# Sheet1.net
KiCad netlist of a schematic drawn in Altium Designer
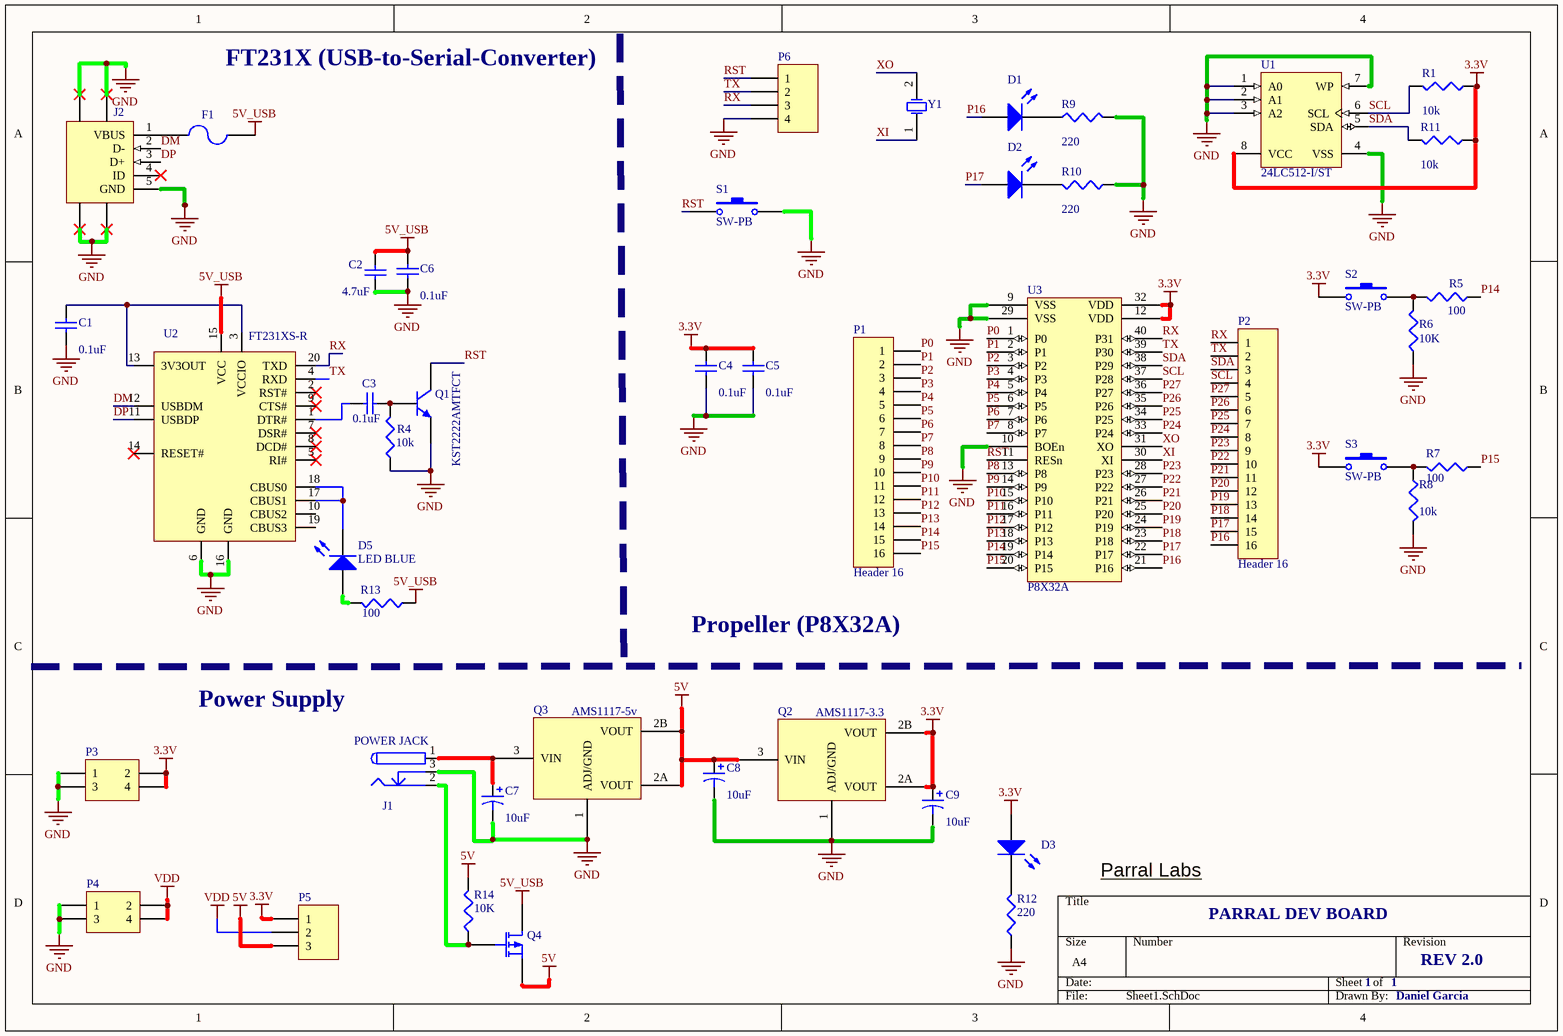
[diagram p0: Sheet1.SchDoc]

(export (version "E")
  (design (tool "Eeschema 10.0.6"))
  (components
    (comp (ref "C1")
      (value "0.1uF")
      (footprint "0603 - Old1")
      (description "0.1uF Capacitor 0603")
      (fields (field (name "PARTNUMBER") "478-1395-1-ND") (field (name "PUBLISHER") "Altium Limited"))
      (libsource (lib "Miscellaneous Devices") (part "Cap Semi"))
    )
    (comp (ref "C2")
      (value "4.7uF")
      (footprint "0603 - Old1")
      (description "4.7µF 25V Ceramic Capacitor X5R 0603")
      (fields
        (field (name "MANUFACTURERPARTNUMBER") "CL21A475KAQNNNE")
        (field (name "PUBLISHER") "Altium Limited")
      )
      (libsource (lib "Miscellaneous Devices") (part "Cap Semi"))
    )
    (comp (ref "C3")
      (value "0.1uF")
      (footprint "0603 - Old1")
      (description "0.1uF Capacitor 0603")
      (fields (field (name "PARTNUMBER") "478-1395-1-ND") (field (name "PUBLISHER") "Altium Limited"))
      (libsource (lib "Miscellaneous Devices") (part "Cap Semi"))
    )
    (comp (ref "C4")
      (value "0.1uF")
      (footprint "0603 - Old1")
      (description "0.1uF Capacitor 0603")
      (fields (field (name "PARTNUMBER") "478-1395-1-ND") (field (name "PUBLISHER") "Altium Limited"))
      (libsource (lib "Miscellaneous Devices") (part "Cap Semi"))
    )
    (comp (ref "C5")
      (value "0.1uF")
      (footprint "0603 - Old1")
      (description "0.1uF Capacitor 0603")
      (fields (field (name "PARTNUMBER") "478-1395-1-ND") (field (name "PUBLISHER") "Altium Limited"))
      (libsource (lib "Miscellaneous Devices") (part "Cap Semi"))
    )
    (comp (ref "C6")
      (value "0.1uF")
      (footprint "0603 - Old1")
      (description "0.1uF Capacitor 0603")
      (fields (field (name "PARTNUMBER") "478-1395-1-ND") (field (name "PUBLISHER") "Altium Limited"))
      (libsource (lib "Miscellaneous Devices") (part "Cap Semi"))
    )
    (comp (ref "C7")
      (value "10uF")
      (footprint "C0805")
      (description "10µF Molded Tantalum Capacitors 10V 0805")
      (fields (field (name "PARTNUMBER") "399-3684-1-ND") (field (name "PUBLISHER") "Altium Limited"))
      (libsource (lib "Miscellaneous Devices") (part "Cap Pol3"))
    )
    (comp (ref "C8")
      (value "10uF")
      (footprint "C0805")
      (description "10µF Molded Tantalum Capacitors 10V 0805")
      (fields (field (name "PARTNUMBER") "399-3684-1-ND") (field (name "PUBLISHER") "Altium Limited"))
      (libsource (lib "Miscellaneous Devices") (part "Cap Pol3"))
    )
    (comp (ref "C9")
      (value "10uF")
      (footprint "C0805")
      (description "10µF Molded Tantalum Capacitors 10V 0805")
      (fields (field (name "PARTNUMBER") "399-3684-1-ND") (field (name "PUBLISHER") "Altium Limited"))
      (libsource (lib "Miscellaneous Devices") (part "Cap Pol3"))
    )
    (comp (ref "D1")
      (value "LED GREEN")
      (footprint "LED-0603")
      (description "LED 0603")
      (fields (field (name "PUBLISHER") "Altium Limited"))
      (libsource (lib "Miscellaneous Devices") (part "LED2"))
    )
    (comp (ref "D2")
      (value "LED BLUE")
      (footprint "LED-0603")
      (description "LED 0603")
      (fields (field (name "PUBLISHER") "Altium Limited"))
      (libsource (lib "Miscellaneous Devices") (part "LED0"))
    )
    (comp (ref "D3")
      (value "LED RED")
      (footprint "LED-0603")
      (description "LED 0603")
      (fields (field (name "PUBLISHER") "Altium Limited"))
      (libsource (lib "Miscellaneous Devices") (part "LED2"))
    )
    (comp (ref "D5")
      (value "LED BLUE")
      (footprint "LED-0603")
      (description "LED 0603")
      (fields (field (name "PUBLISHER") "Altium Limited"))
      (libsource (lib "Miscellaneous Devices") (part "LED0"))
    )
    (comp (ref "F1")
      (value "PTC")
      (footprint "MF-MSMF050-2")
      (description "PTC RESETTABLE .50A 15V 1812")
      (fields
        (field (name "MANUFACTURER PART NUMBER") "MF-MSMF050-2")
        (field (name "MANUFACTURER") "Bourns Inc.")
        (field (name "PUBLISHER") "Altium Limited")
      )
      (libsource (lib "Miscellaneous Devices") (part "Fuse 2"))
    )
    (comp (ref "J1")
      (value "POWER JACK")
      (footprint "PWR JACK")
      (description "POWER JACK 5.5x2.1mm")
      (libsource (lib "dc-powerjack") (part "Component_1"))
    )
    (comp (ref "J2")
      (value "USB - micro B")
      (footprint "micro B USB 2.0")
      (description "CONN USB MICRO B RECPT SMT R/A")
      (fields
        (field (name "MANUFACTURER PART NUMBER") "10118192-0001LF")
        (field (name "PARTNUMBER") "609-4613-1-ND")
      )
      (libsource (lib "MICRO-USB") (part "USB MICRO B RECPT SMT"))
    )
    (comp (ref "P1")
      (value "Header 16")
      (footprint "HDR1X16")
      (description "Header, 16-Pin")
      (fields (field (name "PUBLISHER") "Altium Limited"))
      (libsource (lib "Miscellaneous Connectors") (part "Header 16"))
    )
    (comp (ref "P2")
      (value "Header 16")
      (footprint "HDR1X16")
      (description "Header, 16-Pin")
      (fields (field (name "PUBLISHER") "Altium Limited"))
      (libsource (lib "") (part "Header 16_1"))
    )
    (comp (ref "P3")
      (value "Header 2X2")
      (footprint "HDR2X2")
      (description "Header, 2-Pin, Dual row")
      (fields (field (name "PUBLISHER") "Altium Limited"))
      (libsource (lib "Miscellaneous Connectors") (part "Header 2X2"))
    )
    (comp (ref "P4")
      (value "Header 2X2")
      (footprint "HDR2X2")
      (description "Header, 2-Pin, Dual row")
      (fields (field (name "PUBLISHER") "Altium Limited"))
      (libsource (lib "Miscellaneous Connectors") (part "Header 2X2"))
    )
    (comp (ref "P5")
      (value "Header 3")
      (footprint "HDR1X3")
      (description "Header, 3-Pin")
      (fields (field (name "PUBLISHER") "Altium Limited"))
      (libsource (lib "Miscellaneous Connectors") (part "Header 3"))
    )
    (comp (ref "P6")
      (value "Header 4")
      (footprint "HDR1X4")
      (description "Header, 4-Pin")
      (fields (field (name "PUBLISHER") "Altium Limited"))
      (libsource (lib "Miscellaneous Connectors") (part "Header 4"))
    )
    (comp (ref "Q1")
      (value "KST2222AMTFCT")
      (footprint "SOT-23B_N")
      (description "TRANS NPN 40V 0.6A SOT-23")
      (fields
        (field (name "MANUFACTURER PART NUMBER") "KST2222AMTF")
        (field (name "MANUFACTURER") "Fairchild/ON Semiconductor")
        (field (name "PUBLISHER") "Altium Limited")
      )
      (libsource (lib "Miscellaneous Devices") (part "QNPN"))
    )
    (comp (ref "Q2")
      (value "AMS1117-3.3")
      (footprint "SOT223_M")
      (description "Linear Voltage Regulator IC Positive Fixed 1 Output 3.3V")
      (fields (field (name "MANUFACTURER") "Advanced Monolithic Systems"))
      (libsource (lib "AS1117") (part "AP1117E33GDICT-ND"))
    )
    (comp (ref "Q3")
      (value "AMS1117-5v")
      (footprint "SOT223_M")
      (description "Linear Voltage Regulator IC Positive Fixed 1 Output 3.3V")
      (fields
        (field (name "MANUFACTURER PART NUMBER") "AMS1117-5.0")
        (field (name "MANUFACTURER") "Advanced Monolithic Systems")
      )
      (libsource (lib "AS1117") (part "AP1117E33GDICT-ND"))
    )
    (comp (ref "Q4")
      (value "ZXMP6A13FTA")
      (footprint "SOT-23-3")
      (description "MOSFET P-CH 60V 0.9A SOT23-3")
      (fields (field (name "PUBLISHER") "Altium Limited"))
      (libsource (lib "Miscellaneous Devices") (part "MOSFET-P"))
    )
    (comp (ref "R1")
      (value "10k")
      (footprint "0603-Resistor")
      (description "RES SMD 10K OHM 5% 1/4W 0603")
      (fields (field (name "Comment") "10K") (field (name "PUBLISHER") "Altium Limited"))
      (libsource (lib "Miscellaneous Devices") (part "Res3"))
    )
    (comp (ref "R4")
      (value "10k")
      (footprint "0603-Resistor")
      (description "RES SMD 10K OHM 5% 1/4W 0603")
      (fields (field (name "Comment") "10K") (field (name "PUBLISHER") "Altium Limited"))
      (libsource (lib "Miscellaneous Devices") (part "Res3"))
    )
    (comp (ref "R5")
      (value "100")
      (footprint "0603-Resistor")
      (description "RES SMD 100 OHM 5% 1/4W 0603")
      (fields (field (name "PARTNUMBER") "RMCF1206JT100RCT-ND") (field (name "PUBLISHER") "Altium Limited"))
      (libsource (lib "Miscellaneous Devices") (part "Res3"))
    )
    (comp (ref "R6")
      (value "10K")
      (footprint "0603-Resistor")
      (description "RES SMD 10K OHM 5% 1/4W 0603")
      (fields (field (name "PARTNUMBER") "311-10KERCT-ND") (field (name "PUBLISHER") "Altium Limited"))
      (libsource (lib "Miscellaneous Devices") (part "Res3"))
    )
    (comp (ref "R7")
      (value "100")
      (footprint "0603-Resistor")
      (description "RES SMD 100 OHM 5% 1/4W 0603")
      (fields (field (name "PUBLISHER") "Altium Limited"))
      (libsource (lib "Miscellaneous Devices") (part "Res3"))
    )
    (comp (ref "R8")
      (value "10k")
      (footprint "R-0603:0603-Resistor")
      (description "RES SMD 10K OHM 5% 1/4W 0603")
      (fields (field (name "Comment") "10K") (field (name "PUBLISHER") "Altium Limited"))
      (libsource (lib "Miscellaneous Devices") (part "Res3"))
    )
    (comp (ref "R9")
      (value "220")
      (footprint "0603-Resistor")
      (description "RES SMD 220 OHM 5% 1/4W 0603")
      (fields (field (name "PUBLISHER") "Altium Limited"))
      (libsource (lib "Miscellaneous Devices") (part "Res3"))
    )
    (comp (ref "R10")
      (value "220")
      (footprint "0603-Resistor")
      (description "RES SMD 220 OHM 5% 1/4W 0603")
      (fields (field (name "PUBLISHER") "Altium Limited"))
      (libsource (lib "Miscellaneous Devices") (part "Res3"))
    )
    (comp (ref "R11")
      (value "10k")
      (footprint "0603-Resistor")
      (description "RES SMD 10K OHM 5% 1/4W 0603")
      (fields (field (name "Comment") "10K") (field (name "PUBLISHER") "Altium Limited"))
      (libsource (lib "Miscellaneous Devices") (part "Res3"))
    )
    (comp (ref "R12")
      (value "220")
      (footprint "0603-Resistor")
      (description "RES SMD 220 OHM 5% 1/4W 0603")
      (fields (field (name "PARTNUMBER") "er  P220ECT-ND") (field (name "PUBLISHER") "Altium Limited"))
      (libsource (lib "Miscellaneous Devices") (part "Res3"))
    )
    (comp (ref "R13")
      (value "100")
      (footprint "0603-Resistor")
      (description "RES SMD 100 OHM 5% 1/4W 0603")
      (fields (field (name "PUBLISHER") "Altium Limited"))
      (libsource (lib "Miscellaneous Devices") (part "Res3"))
    )
    (comp (ref "R14")
      (value "10K")
      (footprint "0603-Resistor")
      (description "RES SMD 10K OHM 5% 1/4W 0603")
      (fields (field (name "PUBLISHER") "Altium Limited"))
      (libsource (lib "Miscellaneous Devices") (part "Res3"))
    )
    (comp (ref "S1")
      (value "SW-PB")
      (footprint "PTS810")
      (description "SWITCH TACTILE SPST-NO 0.05A 12V")
      (fields
        (field (name "MANUFACTURER PART NUMBER") "B3U-1000P")
        (field (name "MANUFACTURER") "Omron Electronics Inc-EMC Div")
        (field (name "PUBLISHER") "Altium Limited")
      )
      (libsource (lib "Miscellaneous Devices") (part "SW-PB"))
    )
    (comp (ref "S2")
      (value "SW-PB")
      (footprint "PTS810")
      (description "SWITCH TACTILE SPST-NO 0.05A 12V")
      (fields
        (field (name "MANUFACTURER PART NUMBER") "B3U-1000P")
        (field (name "MANUFACTURER") "Omron Electronics Inc-EMC Div")
        (field (name "PUBLISHER") "Altium Limited")
      )
      (libsource (lib "Miscellaneous Devices") (part "SW-PB"))
    )
    (comp (ref "S3")
      (value "SW-PB")
      (footprint "PTS810")
      (description "SWITCH TACTILE SPST-NO 0.05A 12V")
      (fields
        (field (name "MANUFACTURER PART NUMBER") "B3U-1000P")
        (field (name "MANUFACTURER") "Omron Electronics Inc-EMC Div")
        (field (name "PUBLISHER") "Altium Limited")
      )
      (libsource (lib "Miscellaneous Devices") (part "SW-PB"))
    )
    (comp (ref "U1")
      (value "24LC512-I/ST")
      (footprint "SOIC-8")
      (description "IC EEPROM 512KBIT 400KHZ 8SOIJ")
      (fields
        (field (name "MANUFACTURER PART NUMBER") "24LC512-I/ST-ND")
        (field (name "PUBLISHER") "Altium Limited")
      )
      (libsource (lib "Microchip Memory I2C Serial EEPROM") (part "24LC256-I/ST"))
    )
    (comp (ref "U2")
      (value "FT231XS-R")
      (description "IC USB SERIAL FULL UART 20SSOP")
      (fields
        (field (name "MANUFACTURER") "FTDI, Future Technology Devices International Ltd")
        (field (name "DIGI-KEY PART NUMBER") "768-1129-1-ND")
      )
      (libsource (lib "FT231XS") (part "FT231XS-R"))
    )
    (comp (ref "U3")
      (value "P8X32A")
      (footprint "DIP-40")
      (description "Propeller™ Microcontroller IC 32-Bit 80MHz 32KB (32K x 8) ROM")
      (fields
        (field (name "MANUFACTURER") "PARALLAX INC")
        (field (name "MANUFACTURER PART NUMBER") "P8X32A-D40")
      )
      (libsource (lib "Custon component") (part "P8X32A-D40"))
    )
    (comp (ref "Y1")
      (value "XTAL 5MHZ")
      (footprint "XTAL-2")
      (description "CRYSTAL 5.0000MHZ 18PF T/H")
      (fields
        (field (name "PARTNUMBER") "300-6009-ND")
        (field (name "MANUFACTURER") "Citizen Finedevice Co Ltd")
        (field (name "PUBLISHER") "Altium Limited")
      )
      (libsource (lib "Miscellaneous Devices") (part "XTAL"))
    )
  )
  (nets
    (net (code "1") (name "/DM") (class "Default")
      (node (ref "J2") (pin "2") (pinfunction "D-_2") (pintype "input"))
      (node (ref "U2") (pin "12") (pinfunction "USBDM_12") (pintype "passive"))
    )
    (net (code "2") (name "/DP") (class "Default")
      (node (ref "J2") (pin "3") (pinfunction "D+_3") (pintype "input"))
      (node (ref "U2") (pin "11") (pinfunction "USBDP_11") (pintype "passive"))
    )
    (net (code "3") (name "/P0") (class "Default")
      (node (ref "P1") (pin "1") (pinfunction "1_1") (pintype "passive"))
      (node (ref "U3") (pin "1") (pinfunction "P0_1") (pintype "bidirectional"))
    )
    (net (code "4") (name "/P1") (class "Default")
      (node (ref "P1") (pin "2") (pinfunction "2_2") (pintype "passive"))
      (node (ref "U3") (pin "2") (pinfunction "P1_2") (pintype "bidirectional"))
    )
    (net (code "5") (name "/P2") (class "Default")
      (node (ref "P1") (pin "3") (pinfunction "3_3") (pintype "passive"))
      (node (ref "U3") (pin "3") (pinfunction "P2_3") (pintype "bidirectional"))
    )
    (net (code "6") (name "/P3") (class "Default")
      (node (ref "P1") (pin "4") (pinfunction "4_4") (pintype "passive"))
      (node (ref "U3") (pin "4") (pinfunction "P3_4") (pintype "bidirectional"))
    )
    (net (code "7") (name "/P4") (class "Default")
      (node (ref "P1") (pin "5") (pinfunction "5_5") (pintype "passive"))
      (node (ref "U3") (pin "5") (pinfunction "P4_5") (pintype "bidirectional"))
    )
    (net (code "8") (name "/P5") (class "Default")
      (node (ref "P1") (pin "6") (pinfunction "6_6") (pintype "passive"))
      (node (ref "U3") (pin "6") (pinfunction "P5_6") (pintype "bidirectional"))
    )
    (net (code "9") (name "/P6") (class "Default")
      (node (ref "P1") (pin "7") (pinfunction "7_7") (pintype "passive"))
      (node (ref "U3") (pin "7") (pinfunction "P6_7") (pintype "bidirectional"))
    )
    (net (code "10") (name "/P7") (class "Default")
      (node (ref "P1") (pin "8") (pinfunction "8_8") (pintype "passive"))
      (node (ref "U3") (pin "8") (pinfunction "P7_8") (pintype "bidirectional"))
    )
    (net (code "11") (name "/P8") (class "Default")
      (node (ref "P1") (pin "9") (pinfunction "9_9") (pintype "passive"))
      (node (ref "U3") (pin "13") (pinfunction "P8_13") (pintype "bidirectional"))
    )
    (net (code "12") (name "/P9") (class "Default")
      (node (ref "P1") (pin "10") (pinfunction "10_10") (pintype "passive"))
      (node (ref "U3") (pin "14") (pinfunction "P9_14") (pintype "bidirectional"))
    )
    (net (code "13") (name "/P10") (class "Default")
      (node (ref "P1") (pin "11") (pinfunction "11_11") (pintype "passive"))
      (node (ref "U3") (pin "15") (pinfunction "P10_15") (pintype "bidirectional"))
    )
    (net (code "14") (name "/P11") (class "Default")
      (node (ref "P1") (pin "12") (pinfunction "12_12") (pintype "passive"))
      (node (ref "U3") (pin "16") (pinfunction "P11_16") (pintype "bidirectional"))
    )
    (net (code "15") (name "/P12") (class "Default")
      (node (ref "P1") (pin "13") (pinfunction "13_13") (pintype "passive"))
      (node (ref "U3") (pin "17") (pinfunction "P12_17") (pintype "bidirectional"))
    )
    (net (code "16") (name "/P13") (class "Default")
      (node (ref "P1") (pin "14") (pinfunction "14_14") (pintype "passive"))
      (node (ref "U3") (pin "18") (pinfunction "P13_18") (pintype "bidirectional"))
    )
    (net (code "17") (name "/P14") (class "Default")
      (node (ref "P1") (pin "15") (pinfunction "15_15") (pintype "passive"))
      (node (ref "R5") (pin "1") (pinfunction "1_1") (pintype "passive"))
      (node (ref "U3") (pin "19") (pinfunction "P14_19") (pintype "bidirectional"))
    )
    (net (code "18") (name "/P15") (class "Default")
      (node (ref "P1") (pin "16") (pinfunction "16_16") (pintype "passive"))
      (node (ref "R7") (pin "1") (pinfunction "1_1") (pintype "passive"))
      (node (ref "U3") (pin "20") (pinfunction "P15_20") (pintype "bidirectional"))
    )
    (net (code "19") (name "/P16") (class "Default")
      (node (ref "D1") (pin "1") (pinfunction "A_1") (pintype "passive"))
      (node (ref "P2") (pin "16") (pinfunction "16_16") (pintype "passive"))
      (node (ref "U3") (pin "21") (pinfunction "P16_21") (pintype "bidirectional"))
    )
    (net (code "20") (name "/P17") (class "Default")
      (node (ref "D2") (pin "1") (pinfunction "A_1") (pintype "passive"))
      (node (ref "P2") (pin "15") (pinfunction "15_15") (pintype "passive"))
      (node (ref "U3") (pin "22") (pinfunction "P17_22") (pintype "bidirectional"))
    )
    (net (code "21") (name "/P18") (class "Default")
      (node (ref "P2") (pin "14") (pinfunction "14_14") (pintype "passive"))
      (node (ref "U3") (pin "23") (pinfunction "P18_23") (pintype "bidirectional"))
    )
    (net (code "22") (name "/P19") (class "Default")
      (node (ref "P2") (pin "13") (pinfunction "13_13") (pintype "passive"))
      (node (ref "U3") (pin "24") (pinfunction "P19_24") (pintype "bidirectional"))
    )
    (net (code "23") (name "/P20") (class "Default")
      (node (ref "P2") (pin "12") (pinfunction "12_12") (pintype "passive"))
      (node (ref "U3") (pin "25") (pinfunction "P20_25") (pintype "bidirectional"))
    )
    (net (code "24") (name "/P21") (class "Default")
      (node (ref "P2") (pin "11") (pinfunction "11_11") (pintype "passive"))
      (node (ref "U3") (pin "26") (pinfunction "P21_26") (pintype "bidirectional"))
    )
    (net (code "25") (name "/P22") (class "Default")
      (node (ref "P2") (pin "10") (pinfunction "10_10") (pintype "passive"))
      (node (ref "U3") (pin "27") (pinfunction "P22_27") (pintype "bidirectional"))
    )
    (net (code "26") (name "/P23") (class "Default")
      (node (ref "P2") (pin "9") (pinfunction "9_9") (pintype "passive"))
      (node (ref "U3") (pin "28") (pinfunction "P23_28") (pintype "bidirectional"))
    )
    (net (code "27") (name "/P24") (class "Default")
      (node (ref "P2") (pin "8") (pinfunction "8_8") (pintype "passive"))
      (node (ref "U3") (pin "33") (pinfunction "P24_33") (pintype "bidirectional"))
    )
    (net (code "28") (name "/P25") (class "Default")
      (node (ref "P2") (pin "7") (pinfunction "7_7") (pintype "passive"))
      (node (ref "U3") (pin "34") (pinfunction "P25_34") (pintype "bidirectional"))
    )
    (net (code "29") (name "/P26") (class "Default")
      (node (ref "P2") (pin "6") (pinfunction "6_6") (pintype "passive"))
      (node (ref "U3") (pin "35") (pinfunction "P26_35") (pintype "bidirectional"))
    )
    (net (code "30") (name "/P27") (class "Default")
      (node (ref "P2") (pin "5") (pinfunction "5_5") (pintype "passive"))
      (node (ref "U3") (pin "36") (pinfunction "P27_36") (pintype "bidirectional"))
    )
    (net (code "31") (name "/RST") (class "Default")
      (node (ref "P6") (pin "1") (pinfunction "1_1") (pintype "passive"))
      (node (ref "Q1") (pin "3") (pinfunction "C_3") (pintype "passive"))
      (node (ref "S1") (pin "1") (pinfunction "1_1") (pintype "passive"))
      (node (ref "U3") (pin "11") (pinfunction "RESn_11") (pintype "passive"))
    )
    (net (code "32") (name "/RX") (class "Default")
      (node (ref "P2") (pin "1") (pinfunction "1_1") (pintype "passive"))
      (node (ref "P6") (pin "3") (pinfunction "3_3") (pintype "passive"))
      (node (ref "U2") (pin "20") (pinfunction "TXD_20") (pintype "passive"))
      (node (ref "U3") (pin "40") (pinfunction "P31_40") (pintype "bidirectional"))
    )
    (net (code "33") (name "/SCL") (class "Default")
      (node (ref "P2") (pin "4") (pinfunction "4_4") (pintype "passive"))
      (node (ref "R1") (pin "2") (pinfunction "2_2") (pintype "passive"))
      (node (ref "U1") (pin "6") (pinfunction "SCL_6") (pintype "input"))
      (node (ref "U3") (pin "37") (pinfunction "P28_37") (pintype "bidirectional"))
    )
    (net (code "34") (name "/SDA") (class "Default")
      (node (ref "P2") (pin "3") (pinfunction "3_3") (pintype "passive"))
      (node (ref "R11") (pin "2") (pinfunction "2_2") (pintype "passive"))
      (node (ref "U1") (pin "5") (pinfunction "SDA_5") (pintype "bidirectional"))
      (node (ref "U3") (pin "38") (pinfunction "P29_38") (pintype "bidirectional"))
    )
    (net (code "35") (name "/TX") (class "Default")
      (node (ref "P2") (pin "2") (pinfunction "2_2") (pintype "passive"))
      (node (ref "P6") (pin "2") (pinfunction "2_2") (pintype "passive"))
      (node (ref "U2") (pin "4") (pinfunction "RXD_4") (pintype "passive"))
      (node (ref "U3") (pin "39") (pinfunction "P30_39") (pintype "bidirectional"))
    )
    (net (code "36") (name "/XI") (class "Default")
      (node (ref "U3") (pin "30") (pinfunction "XI_30") (pintype "passive"))
      (node (ref "Y1") (pin "1") (pinfunction "OSC1_1") (pintype "passive"))
    )
    (net (code "37") (name "/XO") (class "Default")
      (node (ref "U3") (pin "31") (pinfunction "XO_31") (pintype "passive"))
      (node (ref "Y1") (pin "2") (pinfunction "OSC2_2") (pintype "passive"))
    )
    (net (code "38") (name "3.3V") (class "Default")
      (node (ref "C4") (pin "2") (pinfunction "2_2") (pintype "passive"))
      (node (ref "C5") (pin "2") (pinfunction "2_2") (pintype "passive"))
      (node (ref "C9") (pin "1") (pinfunction "1_1") (pintype "passive"))
      (node (ref "D3") (pin "1") (pinfunction "A_1") (pintype "passive"))
      (node (ref "P3") (pin "2") (pinfunction "2_2") (pintype "passive"))
      (node (ref "P3") (pin "4") (pinfunction "4_4") (pintype "passive"))
      (node (ref "P5") (pin "1") (pinfunction "1_1") (pintype "passive"))
      (node (ref "Q2") (pin "2A") (pinfunction "VOUT_2A") (pintype "passive"))
      (node (ref "Q2") (pin "2B") (pinfunction "VOUT_2B") (pintype "passive"))
      (node (ref "R1") (pin "1") (pinfunction "1_1") (pintype "passive"))
      (node (ref "R11") (pin "1") (pinfunction "1_1") (pintype "passive"))
      (node (ref "S2") (pin "1") (pinfunction "1_1") (pintype "passive"))
      (node (ref "S3") (pin "1") (pinfunction "1_1") (pintype "passive"))
      (node (ref "U1") (pin "8") (pinfunction "VCC_8") (pintype "power_in"))
      (node (ref "U3") (pin "12") (pinfunction "VDD_12") (pintype "power_in"))
      (node (ref "U3") (pin "32") (pinfunction "VDD_32") (pintype "power_in"))
    )
    (net (code "39") (name "5V") (class "Default")
      (node (ref "C8") (pin "1") (pinfunction "1_1") (pintype "passive"))
      (node (ref "P5") (pin "3") (pinfunction "3_3") (pintype "passive"))
      (node (ref "Q2") (pin "3") (pinfunction "VIN_3") (pintype "passive"))
      (node (ref "Q3") (pin "2A") (pinfunction "VOUT_2A") (pintype "passive"))
      (node (ref "Q3") (pin "2B") (pinfunction "VOUT_2B") (pintype "passive"))
      (node (ref "Q4") (pin "2") (pinfunction "S_2") (pintype "passive"))
      (node (ref "R14") (pin "2") (pinfunction "2_2") (pintype "passive"))
    )
    (net (code "40") (name "5V_USB") (class "Default")
      (node (ref "C2") (pin "2") (pinfunction "2_2") (pintype "passive"))
      (node (ref "C6") (pin "2") (pinfunction "2_2") (pintype "passive"))
      (node (ref "F1") (pin "2") (pinfunction "2_2") (pintype "passive"))
      (node (ref "Q4") (pin "3") (pinfunction "D_3") (pintype "passive"))
      (node (ref "R13") (pin "1") (pinfunction "1_1") (pintype "passive"))
      (node (ref "U2") (pin "15") (pinfunction "VCC_15") (pintype "passive"))
    )
    (net (code "41") (name "GND") (class "Default")
      (node (ref "C1") (pin "1") (pinfunction "1_1") (pintype "passive"))
      (node (ref "C2") (pin "1") (pinfunction "1_1") (pintype "passive"))
      (node (ref "C4") (pin "1") (pinfunction "1_1") (pintype "passive"))
      (node (ref "C5") (pin "1") (pinfunction "1_1") (pintype "passive"))
      (node (ref "C6") (pin "1") (pinfunction "1_1") (pintype "passive"))
      (node (ref "C7") (pin "2") (pinfunction "2_2") (pintype "passive"))
      (node (ref "C8") (pin "2") (pinfunction "2_2") (pintype "passive"))
      (node (ref "C9") (pin "2") (pinfunction "2_2") (pintype "passive"))
      (node (ref "J1") (pin "3") (pinfunction "3_3") (pintype "power_in"))
      (node (ref "J2") (pin "5") (pinfunction "GND_5") (pintype "power_in"))
      (node (ref "J2") (pin "6") (pintype "passive"))
      (node (ref "J2") (pin "7") (pintype "passive"))
      (node (ref "J2") (pin "8") (pintype "passive"))
      (node (ref "J2") (pin "9") (pintype "passive"))
      (node (ref "P3") (pin "1") (pinfunction "1_1") (pintype "passive"))
      (node (ref "P3") (pin "3") (pinfunction "3_3") (pintype "passive"))
      (node (ref "P4") (pin "1") (pinfunction "1_1") (pintype "passive"))
      (node (ref "P4") (pin "3") (pinfunction "3_3") (pintype "passive"))
      (node (ref "P6") (pin "4") (pinfunction "4_4") (pintype "passive"))
      (node (ref "Q1") (pin "2") (pinfunction "E_2") (pintype "passive"))
      (node (ref "Q2") (pin "1") (pinfunction "ADJ/GND_1") (pintype "passive"))
      (node (ref "Q3") (pin "1") (pinfunction "ADJ/GND_1") (pintype "passive"))
      (node (ref "R10") (pin "1") (pinfunction "1_1") (pintype "passive"))
      (node (ref "R12") (pin "1") (pinfunction "1_1") (pintype "passive"))
      (node (ref "R4") (pin "1") (pinfunction "1_1") (pintype "passive"))
      (node (ref "R6") (pin "1") (pinfunction "1_1") (pintype "passive"))
      (node (ref "R8") (pin "2") (pinfunction "2_2") (pintype "passive"))
      (node (ref "R9") (pin "2") (pinfunction "2_2") (pintype "passive"))
      (node (ref "S1") (pin "2") (pinfunction "2_2") (pintype "passive"))
      (node (ref "U1") (pin "1") (pinfunction "A0_1") (pintype "input"))
      (node (ref "U1") (pin "2") (pinfunction "A1_2") (pintype "input"))
      (node (ref "U1") (pin "3") (pinfunction "A2_3") (pintype "input"))
      (node (ref "U1") (pin "4") (pinfunction "VSS_4") (pintype "power_in"))
      (node (ref "U1") (pin "7") (pinfunction "WP_7") (pintype "input"))
      (node (ref "U2") (pin "16") (pinfunction "GND_16") (pintype "passive"))
      (node (ref "U2") (pin "6") (pinfunction "GND_6") (pintype "passive"))
      (node (ref "U3") (pin "10") (pinfunction "BOEn_10") (pintype "passive"))
      (node (ref "U3") (pin "29") (pinfunction "VSS_29") (pintype "power_in"))
      (node (ref "U3") (pin "9") (pinfunction "VSS_9") (pintype "power_in"))
    )
    (net (code "42") (name "Net-(D1-K)") (class "Default")
      (node (ref "D1") (pin "2") (pinfunction "K_2") (pintype "passive"))
      (node (ref "R9") (pin "1") (pinfunction "1_1") (pintype "passive"))
    )
    (net (code "43") (name "Net-(D2-K)") (class "Default")
      (node (ref "D2") (pin "2") (pinfunction "K_2") (pintype "passive"))
      (node (ref "R10") (pin "2") (pinfunction "2_2") (pintype "passive"))
    )
    (net (code "44") (name "Net-(D3-K)") (class "Default")
      (node (ref "D3") (pin "2") (pinfunction "K_2") (pintype "passive"))
      (node (ref "R12") (pin "2") (pinfunction "2_2") (pintype "passive"))
    )
    (net (code "45") (name "Net-(D5-A)") (class "Default")
      (node (ref "D5") (pin "1") (pinfunction "A_1") (pintype "passive"))
      (node (ref "R13") (pin "2") (pinfunction "2_2") (pintype "passive"))
    )
    (net (code "46") (name "Net-(D5-K)") (class "Default")
      (node (ref "D5") (pin "2") (pinfunction "K_2") (pintype "passive"))
      (node (ref "U2") (pin "17") (pinfunction "CBUS1_17") (pintype "passive"))
      (node (ref "U2") (pin "18") (pinfunction "CBUS0_18") (pintype "passive"))
    )
    (net (code "47") (name "Net-(J2-VBUS)") (class "Default")
      (node (ref "F1") (pin "1") (pinfunction "1_1") (pintype "passive"))
      (node (ref "J2") (pin "1") (pinfunction "VBUS_1") (pintype "power_in"))
    )
    (net (code "48") (name "Net-(Q1-B)") (class "Default")
      (node (ref "C3") (pin "2") (pinfunction "2_2") (pintype "passive"))
      (node (ref "Q1") (pin "1") (pinfunction "B_1") (pintype "passive"))
      (node (ref "R4") (pin "2") (pinfunction "2_2") (pintype "passive"))
    )
    (net (code "49") (name "Net-(Q3-VIN)") (class "Default")
      (node (ref "C7") (pin "1") (pinfunction "1_1") (pintype "passive"))
      (node (ref "J1") (pin "1") (pinfunction "1_1") (pintype "power_in"))
      (node (ref "Q3") (pin "3") (pinfunction "VIN_3") (pintype "passive"))
    )
    (net (code "50") (name "Net-(Q4-G)") (class "Default")
      (node (ref "J1") (pin "2") (pinfunction "2_2") (pintype "power_in"))
      (node (ref "Q4") (pin "1") (pinfunction "G_1") (pintype "passive"))
      (node (ref "R14") (pin "1") (pinfunction "1_1") (pintype "passive"))
    )
    (net (code "51") (name "Net-(R5-Pad2)") (class "Default")
      (node (ref "R5") (pin "2") (pinfunction "2_2") (pintype "passive"))
      (node (ref "R6") (pin "2") (pinfunction "2_2") (pintype "passive"))
      (node (ref "S2") (pin "2") (pinfunction "2_2") (pintype "passive"))
    )
    (net (code "52") (name "Net-(R7-Pad2)") (class "Default")
      (node (ref "R7") (pin "2") (pinfunction "2_2") (pintype "passive"))
      (node (ref "R8") (pin "1") (pinfunction "1_1") (pintype "passive"))
      (node (ref "S3") (pin "2") (pinfunction "2_2") (pintype "passive"))
    )
    (net (code "53") (name "Net-(U2-3V3OUT)") (class "Default")
      (node (ref "C1") (pin "2") (pinfunction "2_2") (pintype "passive"))
      (node (ref "U2") (pin "13") (pinfunction "3V3OUT_13") (pintype "passive"))
      (node (ref "U2") (pin "3") (pinfunction "VCCIO_3") (pintype "passive"))
    )
    (net (code "54") (name "Net-(U2-DTR#)") (class "Default")
      (node (ref "C3") (pin "1") (pinfunction "1_1") (pintype "passive"))
      (node (ref "U2") (pin "1") (pinfunction "DTR#_1") (pintype "passive"))
    )
    (net (code "55") (name "VDD") (class "Default")
      (node (ref "P4") (pin "2") (pinfunction "2_2") (pintype "passive"))
      (node (ref "P4") (pin "4") (pinfunction "4_4") (pintype "passive"))
      (node (ref "P5") (pin "2") (pinfunction "2_2") (pintype "passive"))
    )
    (net (code "56") (name "unconnected-(J2-ID-Pad4)") (class "Default")
      (node (ref "J2") (pin "4") (pinfunction "ID_4") (pintype "passive+no_connect"))
    )
    (net (code "57") (name "unconnected-(U2-CBUS2-Pad10)") (class "Default")
      (node (ref "U2") (pin "10") (pinfunction "CBUS2_10") (pintype "passive"))
    )
    (net (code "58") (name "unconnected-(U2-CBUS3-Pad19)") (class "Default")
      (node (ref "U2") (pin "19") (pinfunction "CBUS3_19") (pintype "passive"))
    )
    (net (code "59") (name "unconnected-(U2-CTS#-Pad9)") (class "Default")
      (node (ref "U2") (pin "9") (pinfunction "CTS#_9") (pintype "passive+no_connect"))
    )
    (net (code "60") (name "unconnected-(U2-DCD#-Pad8)") (class "Default")
      (node (ref "U2") (pin "8") (pinfunction "DCD#_8") (pintype "passive+no_connect"))
    )
    (net (code "61") (name "unconnected-(U2-DSR#-Pad7)") (class "Default")
      (node (ref "U2") (pin "7") (pinfunction "DSR#_7") (pintype "passive+no_connect"))
    )
    (net (code "62") (name "unconnected-(U2-RESET#-Pad14)") (class "Default")
      (node (ref "U2") (pin "14") (pinfunction "RESET#_14") (pintype "passive+no_connect"))
    )
    (net (code "63") (name "unconnected-(U2-RI#-Pad5)") (class "Default")
      (node (ref "U2") (pin "5") (pinfunction "RI#_5") (pintype "passive+no_connect"))
    )
    (net (code "64") (name "unconnected-(U2-RST#-Pad2)") (class "Default")
      (node (ref "U2") (pin "2") (pinfunction "RST#_2") (pintype "passive+no_connect"))
    )
  )
)
